# RTI-Dome-eth-RP2040.net
KiCad netlist of a schematic drawn in EAGLE
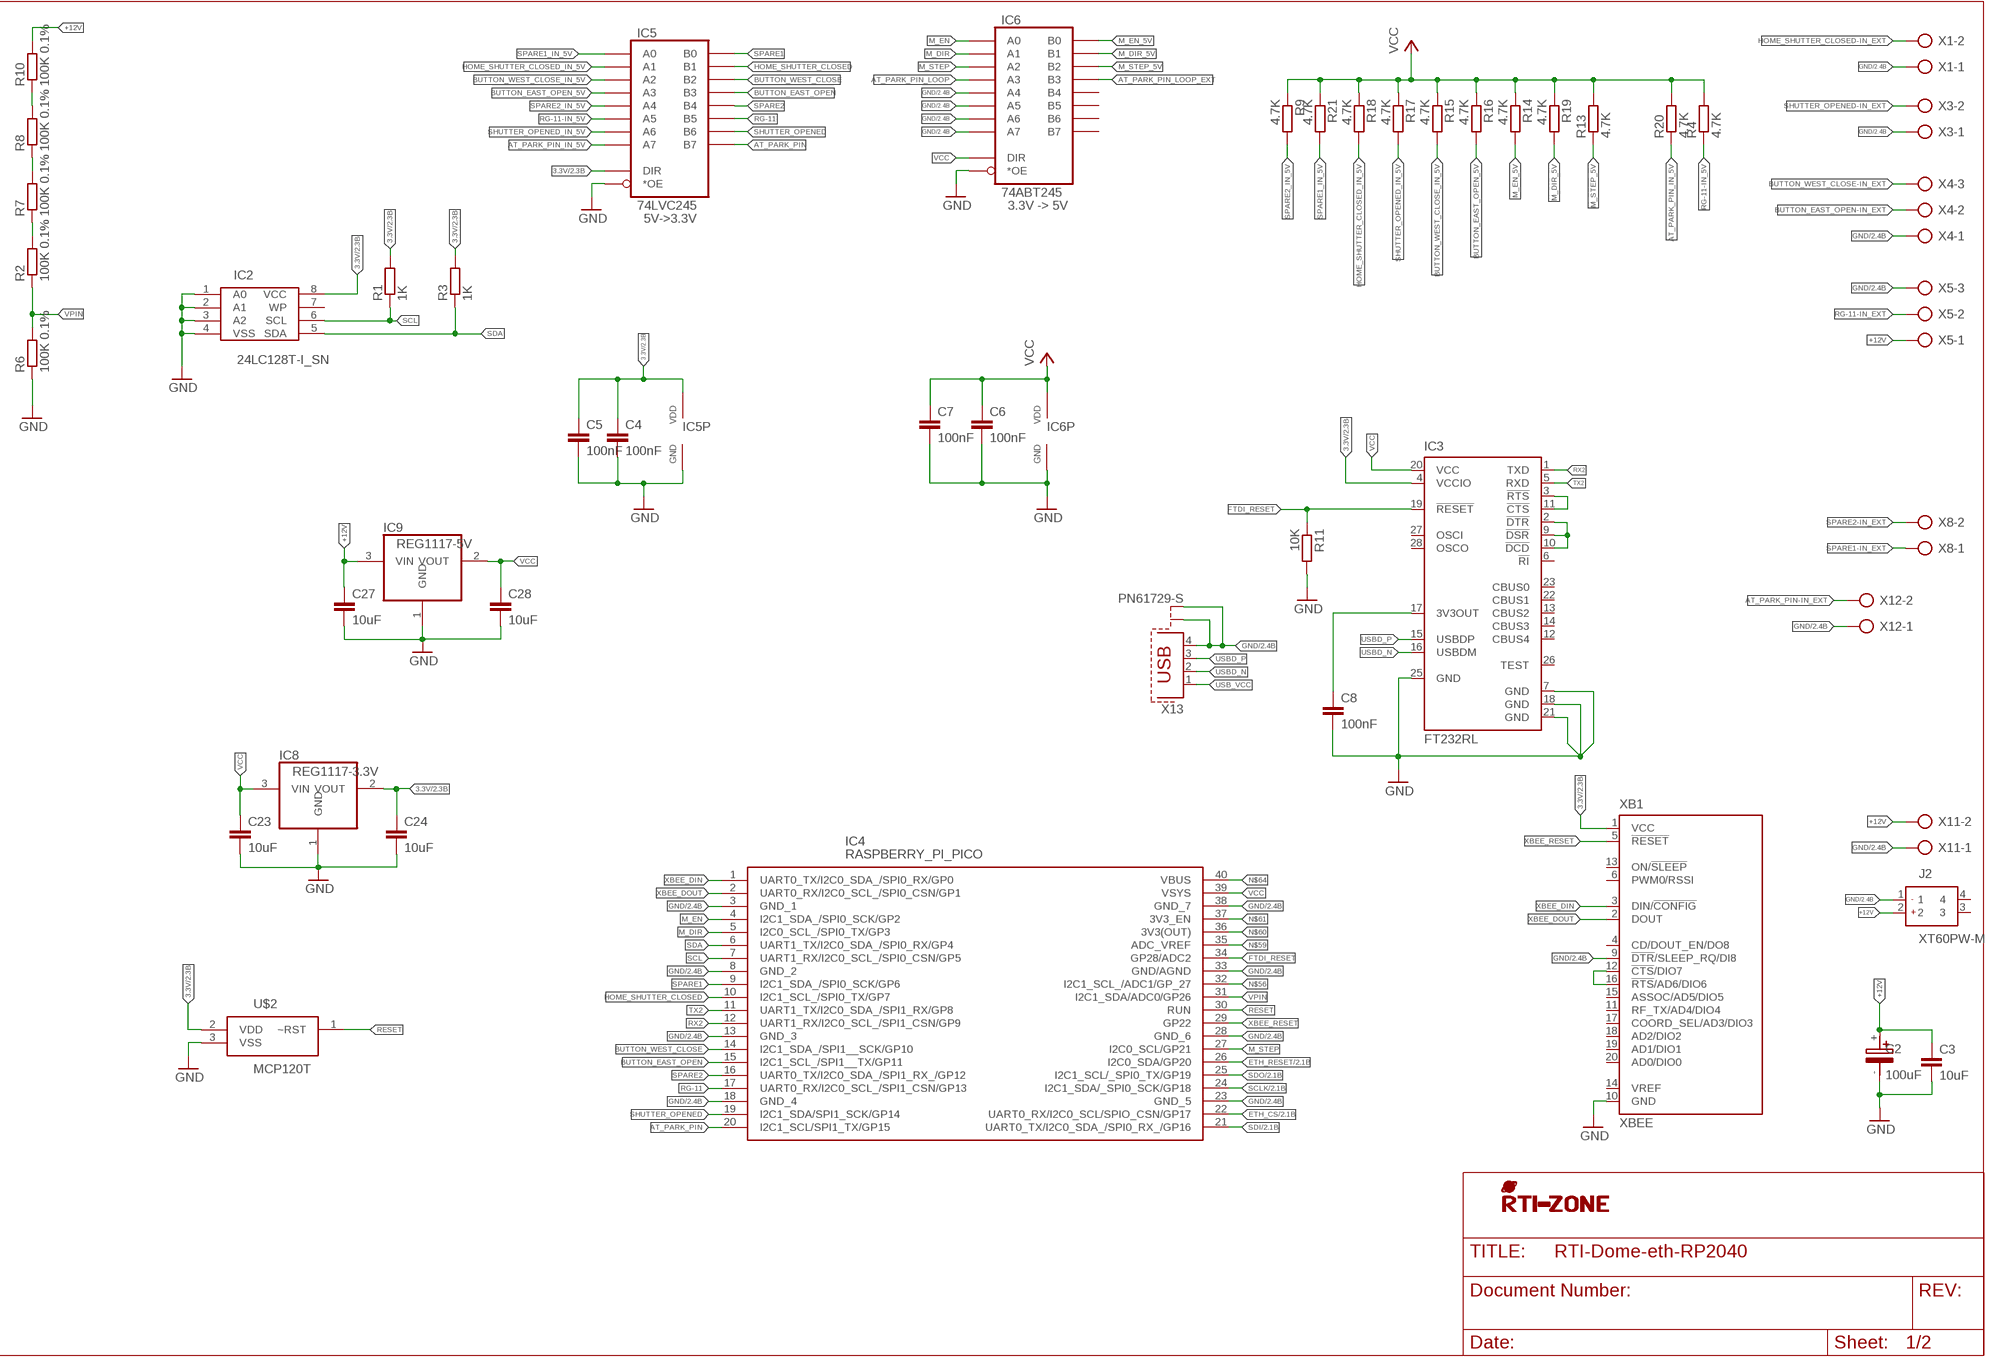
[diagram p0: schematic, sheet 1, part 1 of 2]
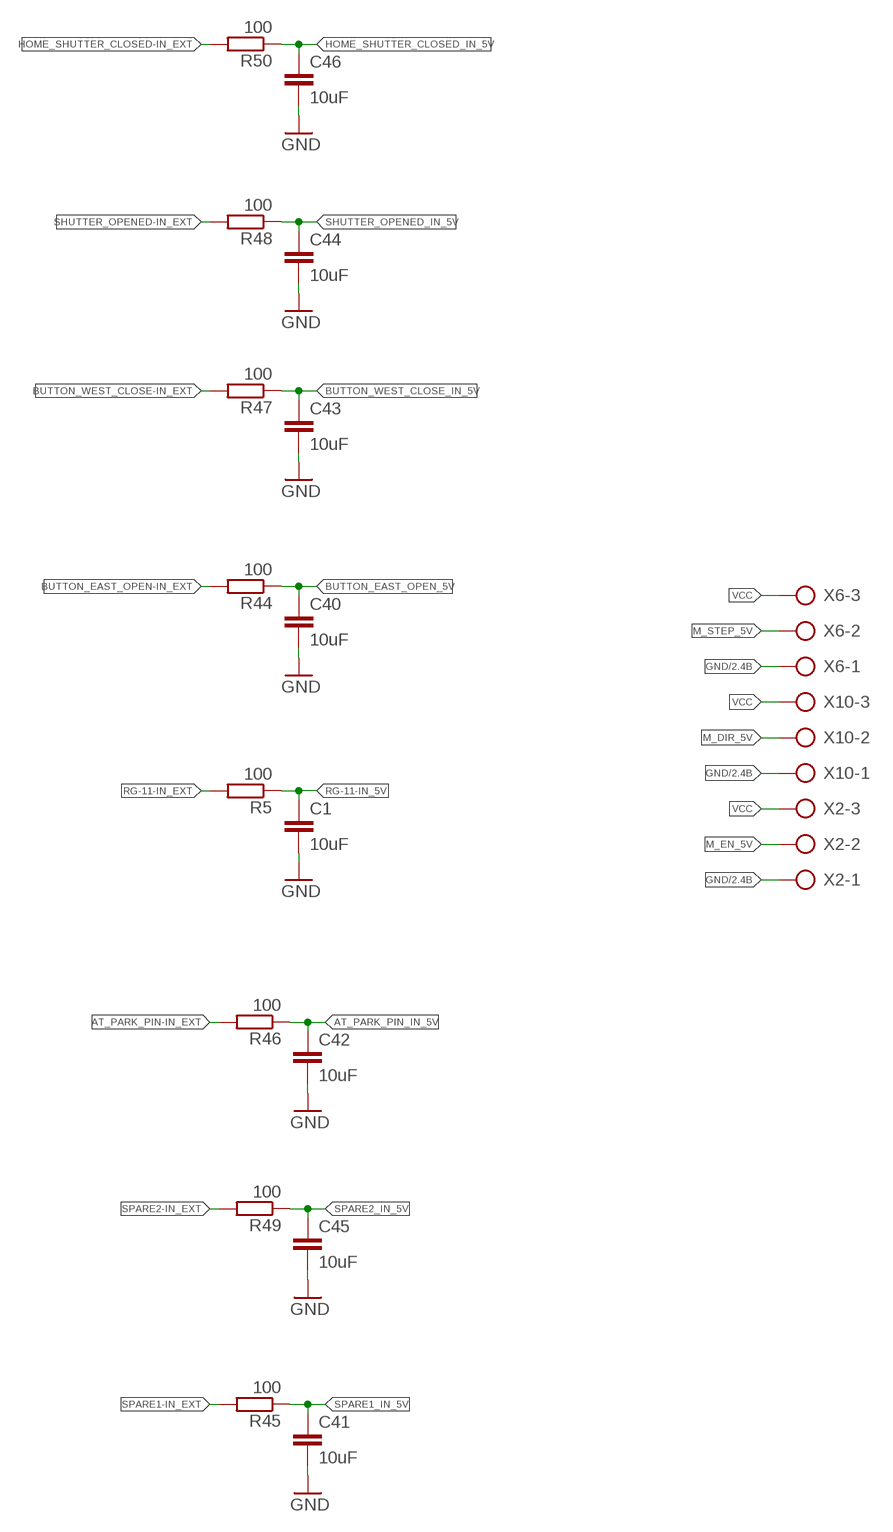
[diagram p1: schematic, sheet 1, part 2 of 2]
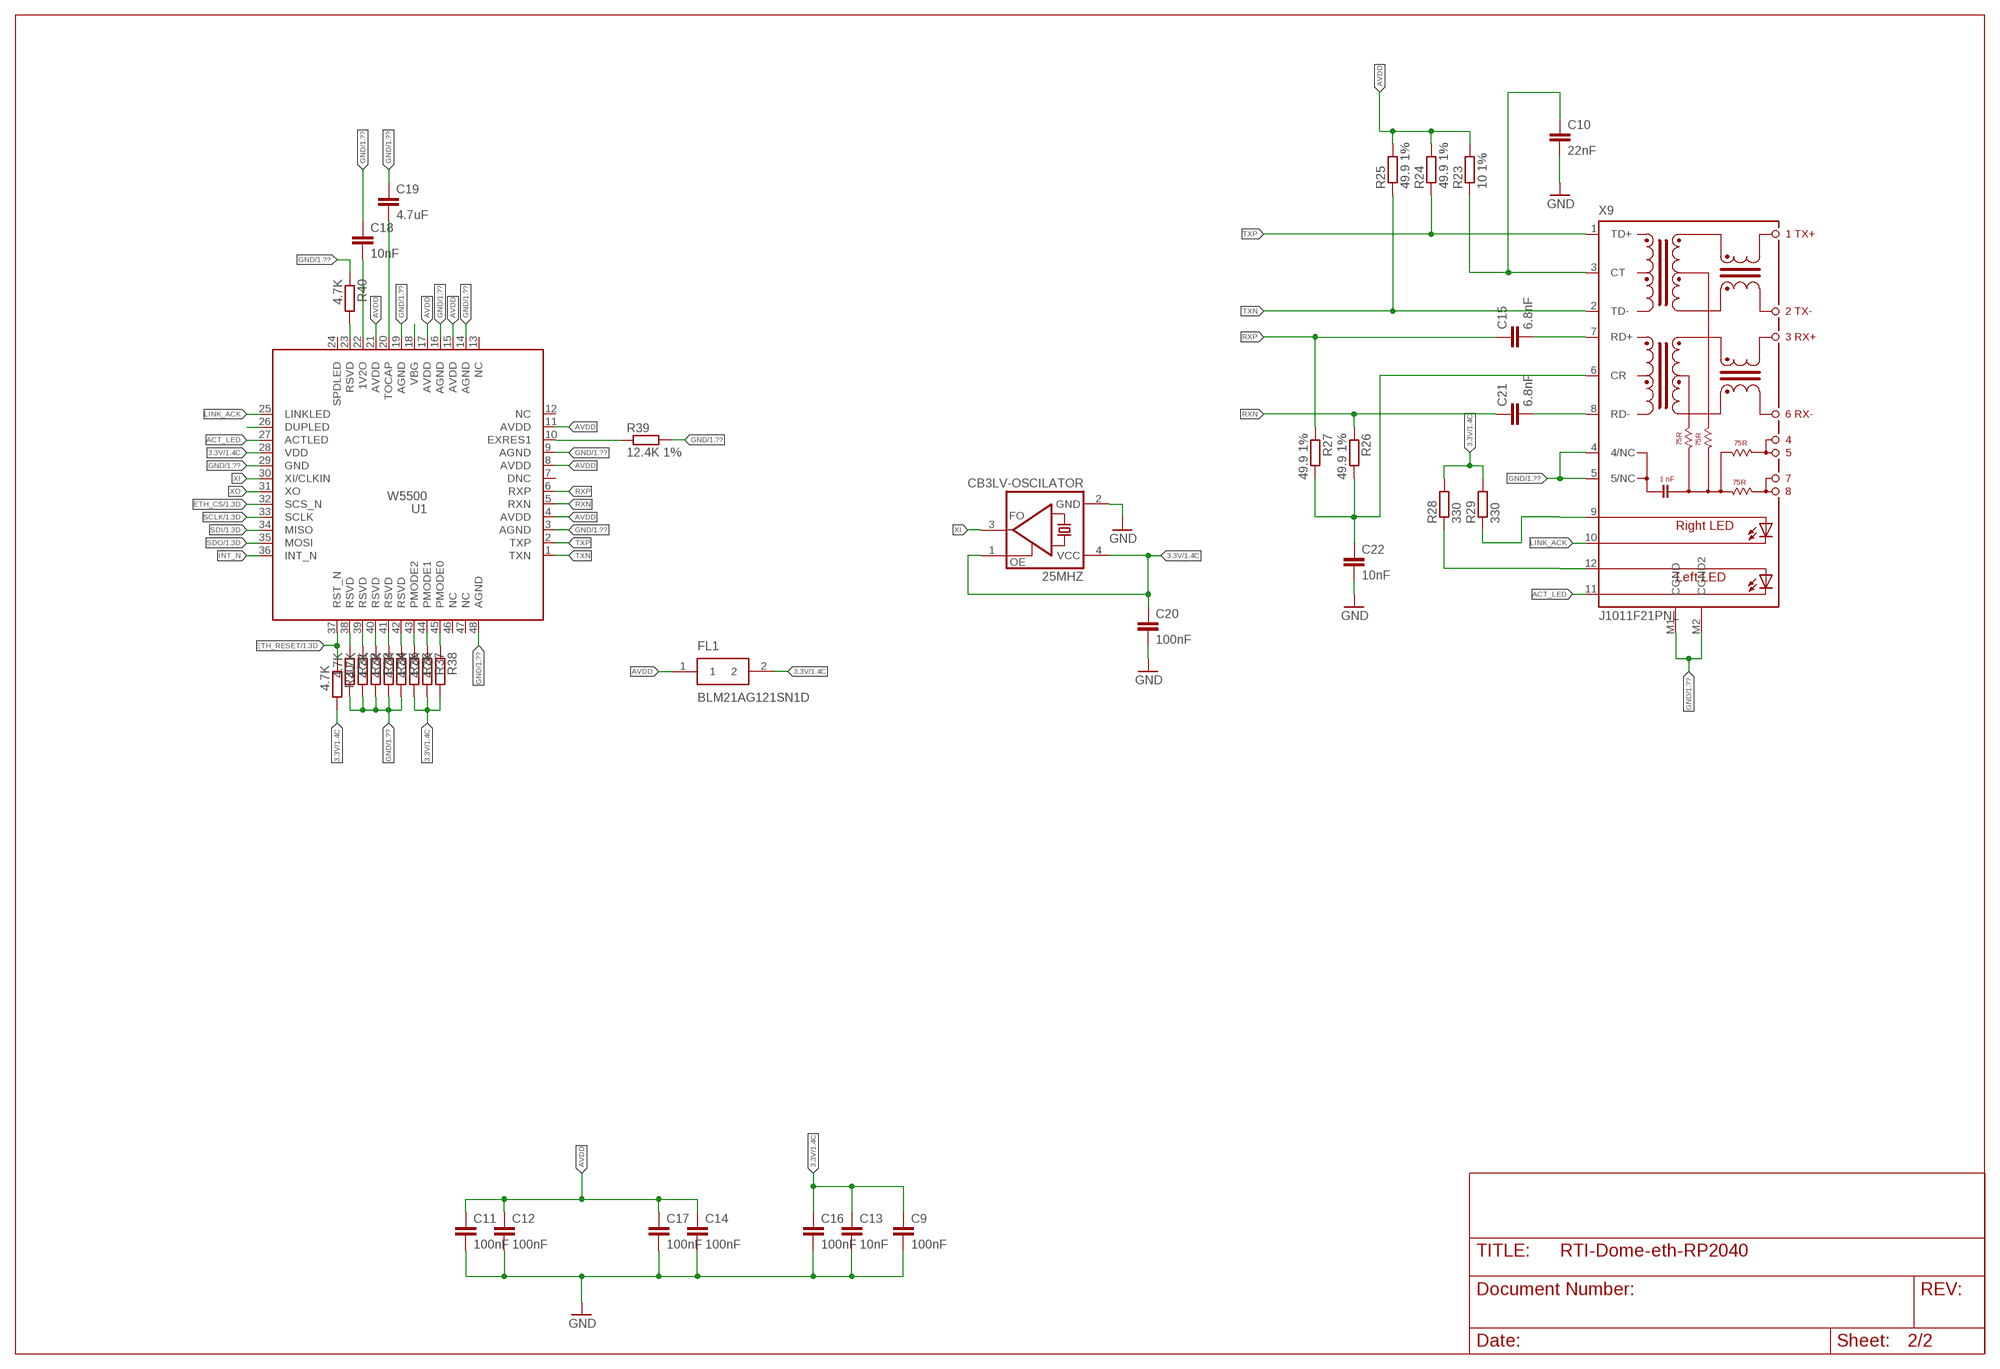
[diagram p2: schematic, sheet 2]

(export (version "E")
  (design (tool "Eeschema 10.0.6"))
  (components
    (comp (ref "C1")
      (value "10uF")
      (footprint "eagle-import:C0805")
      (fields (field (name "MPN") "CC0805KKX5R8BB106"))
      (libsource (lib "eagle-import") (part "C-EUC0805"))
    )
    (comp (ref "C2")
      (value "100uF")
      (footprint "eagle-import:UD-10X10_NICHICON")
      (fields (field (name "MPN") "MAL215099804E3"))
      (libsource (lib "eagle-import") (part "MAL215099804E3{dblquote}{dblquote}"))
    )
    (comp (ref "C3")
      (value "10uF")
      (footprint "eagle-import:C0805")
      (fields (field (name "MPN") "CC0805KKX5R8BB106"))
      (libsource (lib "eagle-import") (part "C-EUC0805"))
    )
    (comp (ref "C4")
      (value "100nF")
      (footprint "eagle-import:C0805")
      (fields (field (name "MPN") "0805YD104KAT2A"))
      (libsource (lib "eagle-import") (part "C-EUC0805"))
    )
    (comp (ref "C5")
      (value "100nF")
      (footprint "eagle-import:C0805")
      (fields (field (name "MPN") "0805YD104KAT2A"))
      (libsource (lib "eagle-import") (part "C-EUC0805"))
    )
    (comp (ref "C6")
      (value "100nF")
      (footprint "eagle-import:C0805")
      (fields (field (name "MPN") "0805YD104KAT2A"))
      (libsource (lib "eagle-import") (part "C-EUC0805"))
    )
    (comp (ref "C7")
      (value "100nF")
      (footprint "eagle-import:C0805")
      (fields (field (name "MPN") "0805YD104KAT2A"))
      (libsource (lib "eagle-import") (part "C-EUC0805"))
    )
    (comp (ref "C8")
      (value "100nF")
      (footprint "eagle-import:C0805")
      (fields (field (name "MPN") "0805YD104KAT2A"))
      (libsource (lib "eagle-import") (part "C-EUC0805"))
    )
    (comp (ref "C23")
      (value "10uF")
      (footprint "eagle-import:C0805")
      (fields (field (name "MPN") "CC0805KKX5R8BB106"))
      (libsource (lib "eagle-import") (part "C-EUC0805"))
    )
    (comp (ref "C24")
      (value "10uF")
      (footprint "eagle-import:C0805")
      (fields (field (name "MPN") "CC0805KKX5R8BB106"))
      (libsource (lib "eagle-import") (part "C-EUC0805"))
    )
    (comp (ref "C27")
      (value "10uF")
      (footprint "eagle-import:C0805")
      (fields (field (name "MPN") "CC0805KKX5R8BB106"))
      (libsource (lib "eagle-import") (part "C-EUC0805"))
    )
    (comp (ref "C28")
      (value "10uF")
      (footprint "eagle-import:C0805")
      (fields (field (name "MPN") "CC0805KKX5R8BB106"))
      (libsource (lib "eagle-import") (part "C-EUC0805"))
    )
    (comp (ref "C40")
      (value "10uF")
      (footprint "eagle-import:C0805")
      (fields (field (name "MPN") "CC0805KKX5R8BB106"))
      (libsource (lib "eagle-import") (part "C-EUC0805"))
    )
    (comp (ref "C41")
      (value "10uF")
      (footprint "eagle-import:C0805")
      (fields (field (name "MPN") "CC0805KKX5R8BB106"))
      (libsource (lib "eagle-import") (part "C-EUC0805"))
    )
    (comp (ref "C42")
      (value "10uF")
      (footprint "eagle-import:C0805")
      (fields (field (name "MPN") "CC0805KKX5R8BB106"))
      (libsource (lib "eagle-import") (part "C-EUC0805"))
    )
    (comp (ref "C43")
      (value "10uF")
      (footprint "eagle-import:C0805")
      (fields (field (name "MPN") "CC0805KKX5R8BB106"))
      (libsource (lib "eagle-import") (part "C-EUC0805"))
    )
    (comp (ref "C44")
      (value "10uF")
      (footprint "eagle-import:C0805")
      (fields (field (name "MPN") "CC0805KKX5R8BB106"))
      (libsource (lib "eagle-import") (part "C-EUC0805"))
    )
    (comp (ref "C45")
      (value "10uF")
      (footprint "eagle-import:C0805")
      (fields (field (name "MPN") "CC0805KKX5R8BB106"))
      (libsource (lib "eagle-import") (part "C-EUC0805"))
    )
    (comp (ref "C46")
      (value "10uF")
      (footprint "eagle-import:C0805")
      (fields (field (name "MPN") "CC0805KKX5R8BB106"))
      (libsource (lib "eagle-import") (part "C-EUC0805"))
    )
    (comp (ref "IC2")
      (value "24LC128T-I_SN")
      (footprint "eagle-import:SOIC127P600X175-8N")
      (fields
        (field (name "ARROW_PART_NUMBER") "24LC128T-I/SN")
        (field (name "MOUSER_PART_NUMBER") "579-24LC128T-I/SN")
      )
      (libsource (lib "eagle-import") (part "24LC128T-I_SN"))
    )
    (comp (ref "IC3")
      (value "FT232RL")
      (footprint "eagle-import:SSOP28")
      (fields (field (name "MPN") "FT232RL-REEL"))
      (libsource (lib "eagle-import") (part "FT232RL"))
    )
    (comp (ref "IC4")
      (value "RASPBERRY_PI_PICO")
      (footprint "eagle-import:RASPBERRYPIPICO")
      (description "RASPBERRY-PI - RASPBERRY PI PICO - Raspberry Pi Board, Raspberry Pi Pic, RP2040, 32bit, ARM Cortex-M0+")
      (fields
        (field (name "MANUFACTURER_PART_NUMBER") "RASPBERRY PI PICO W")
        (field (name "MANUFACTURER_NAME") "RASPBERRY-PI PICO")
        (field (name "MANUFACTURER_PART_NUMBER_1") "SC0916")
        (field (name "MOUSER_PART_NUMBER") "SC0915")
        (field (name "MPN") "SC0916")
      )
      (libsource (lib "eagle-import") (part "RASPBERRY_PI_PICO"))
    )
    (comp (ref "IC5")
      (value "74LVC245")
      (footprint "eagle-import:TSSOP20")
      (fields (field (name "MPN") "SN74LVC245APWR"))
      (libsource (lib "eagle-import") (part "74245LVC"))
    )
    (comp (ref "IC6")
      (value "74ABT245")
      (footprint "eagle-import:TSSOP20")
      (fields (field (name "MPN") "74ABT245PW,118"))
      (libsource (lib "eagle-import") (part "74245ABT"))
    )
    (comp (ref "IC8")
      (value "REG1117-3.3V")
      (footprint "eagle-import:SOT223")
      (fields (field (name "MPN") "REG1117") (field (name "MPN_1") "REG1117-3.3/2K5"))
      (libsource (lib "eagle-import") (part "REG1117"))
    )
    (comp (ref "IC9")
      (value "REG1117-5V")
      (footprint "eagle-import:SOT223")
      (fields (field (name "MPN") "REG1117") (field (name "MPN_1") "REG1117-3.3/2K5"))
      (libsource (lib "eagle-import") (part "REG1117"))
    )
    (comp (ref "J2")
      (value "XT60PW-M")
      (footprint "eagle-import:XT60PWM")
      (libsource (lib "eagle-import") (part "XT60PW-M"))
    )
    (comp (ref "R1")
      (value "1K")
      (footprint "eagle-import:R0805")
      (fields (field (name "MPN") "RT0805FRE071KL"))
      (libsource (lib "eagle-import") (part "R-EU_R0805"))
    )
    (comp (ref "R2")
      (value "100K 0.1%")
      (footprint "eagle-import:R0805")
      (fields (field (name "MPN") "AT0805BRD07100KL"))
      (libsource (lib "eagle-import") (part "R-EU_R0805"))
    )
    (comp (ref "R3")
      (value "1K")
      (footprint "eagle-import:R0805")
      (fields (field (name "MPN") "RT0805FRE071KL"))
      (libsource (lib "eagle-import") (part "R-EU_R0805"))
    )
    (comp (ref "R4")
      (value "4.7K")
      (footprint "eagle-import:R0805")
      (fields (field (name "MPN") "RT0805FRE074K7L"))
      (libsource (lib "eagle-import") (part "R-EU_R0805"))
    )
    (comp (ref "R5")
      (value "100")
      (footprint "eagle-import:R0805")
      (fields (field (name "MPN") "RT0805FRD07100RL"))
      (libsource (lib "eagle-import") (part "R-EU_R0805"))
    )
    (comp (ref "R6")
      (value "100K 0.1%")
      (footprint "eagle-import:R0805")
      (fields (field (name "MPN") "AT0805BRD07100KL"))
      (libsource (lib "eagle-import") (part "R-EU_R0805"))
    )
    (comp (ref "R7")
      (value "100K 0.1%")
      (footprint "eagle-import:R0805")
      (fields (field (name "MPN") "AT0805BRD07100KL"))
      (libsource (lib "eagle-import") (part "R-EU_R0805"))
    )
    (comp (ref "R8")
      (value "100K 0.1%")
      (footprint "eagle-import:R0805")
      (fields (field (name "MPN") "AT0805BRD07100KL"))
      (libsource (lib "eagle-import") (part "R-EU_R0805"))
    )
    (comp (ref "R9")
      (value "4.7K")
      (footprint "eagle-import:R0805")
      (fields (field (name "MPN") "RT0805FRE074K7L"))
      (libsource (lib "eagle-import") (part "R-EU_R0805"))
    )
    (comp (ref "R10")
      (value "100K 0.1%")
      (footprint "eagle-import:R0805")
      (fields (field (name "MPN") "AT0805BRD07100KL"))
      (libsource (lib "eagle-import") (part "R-EU_R0805"))
    )
    (comp (ref "R11")
      (value "10K")
      (footprint "eagle-import:R0805")
      (fields (field (name "MPN") "RT0805FRE0710KL"))
      (libsource (lib "eagle-import") (part "R-EU_R0805"))
    )
    (comp (ref "R13")
      (value "4.7K")
      (footprint "eagle-import:R0805")
      (fields (field (name "MPN") "RT0805FRE074K7L"))
      (libsource (lib "eagle-import") (part "R-EU_R0805"))
    )
    (comp (ref "R14")
      (value "4.7K")
      (footprint "eagle-import:R0805")
      (fields (field (name "MPN") "RT0805FRE074K7L"))
      (libsource (lib "eagle-import") (part "R-EU_R0805"))
    )
    (comp (ref "R15")
      (value "4.7K")
      (footprint "eagle-import:R0805")
      (fields (field (name "MPN") "RT0805FRE074K7L"))
      (libsource (lib "eagle-import") (part "R-EU_R0805"))
    )
    (comp (ref "R16")
      (value "4.7K")
      (footprint "eagle-import:R0805")
      (fields (field (name "MPN") "RT0805FRE074K7L"))
      (libsource (lib "eagle-import") (part "R-EU_R0805"))
    )
    (comp (ref "R17")
      (value "4.7K")
      (footprint "eagle-import:R0805")
      (fields (field (name "MPN") "RT0805FRE074K7L"))
      (libsource (lib "eagle-import") (part "R-EU_R0805"))
    )
    (comp (ref "R18")
      (value "4.7K")
      (footprint "eagle-import:R0805")
      (fields (field (name "MPN") "RT0805FRE074K7L"))
      (libsource (lib "eagle-import") (part "R-EU_R0805"))
    )
    (comp (ref "R19")
      (value "4.7K")
      (footprint "eagle-import:R0805")
      (fields (field (name "MPN") "RT0805FRE074K7L"))
      (libsource (lib "eagle-import") (part "R-EU_R0805"))
    )
    (comp (ref "R20")
      (value "4.7K")
      (footprint "eagle-import:R0805")
      (fields (field (name "MPN") "RT0805FRE074K7L"))
      (libsource (lib "eagle-import") (part "R-EU_R0805"))
    )
    (comp (ref "R21")
      (value "4.7K")
      (footprint "eagle-import:R0805")
      (fields (field (name "MPN") "RT0805FRE074K7L"))
      (libsource (lib "eagle-import") (part "R-EU_R0805"))
    )
    (comp (ref "R44")
      (value "100")
      (footprint "eagle-import:R0805")
      (fields (field (name "MPN") "RT0805FRD07100RL"))
      (libsource (lib "eagle-import") (part "R-EU_R0805"))
    )
    (comp (ref "R45")
      (value "100")
      (footprint "eagle-import:R0805")
      (fields (field (name "MPN") "RT0805FRD07100RL"))
      (libsource (lib "eagle-import") (part "R-EU_R0805"))
    )
    (comp (ref "R46")
      (value "100")
      (footprint "eagle-import:R0805")
      (fields (field (name "MPN") "RT0805FRD07100RL"))
      (libsource (lib "eagle-import") (part "R-EU_R0805"))
    )
    (comp (ref "R47")
      (value "100")
      (footprint "eagle-import:R0805")
      (fields (field (name "MPN") "RT0805FRD07100RL"))
      (libsource (lib "eagle-import") (part "R-EU_R0805"))
    )
    (comp (ref "R48")
      (value "100")
      (footprint "eagle-import:R0805")
      (fields (field (name "MPN") "RT0805FRD07100RL"))
      (libsource (lib "eagle-import") (part "R-EU_R0805"))
    )
    (comp (ref "R49")
      (value "100")
      (footprint "eagle-import:R0805")
      (fields (field (name "MPN") "RT0805FRD07100RL"))
      (libsource (lib "eagle-import") (part "R-EU_R0805"))
    )
    (comp (ref "R50")
      (value "100")
      (footprint "eagle-import:R0805")
      (fields (field (name "MPN") "RT0805FRD07100RL"))
      (libsource (lib "eagle-import") (part "R-EU_R0805"))
    )
    (comp (ref "U$2")
      (value "MCP120T")
      (footprint "eagle-import:SOT95P237X112-3N")
      (fields
        (field (name "MANUFACTURER_PART_NUMBER") "MCP120T-315I/TT")
        (field (name "MOUSER_PART_NUMBER") "579-MCP120T-315I/TT")
        (field (name "MPN") "MCP120T-270I/TT")
      )
      (libsource (lib "eagle-import") (part "MCP120T"))
    )
    (comp (ref "U$4")
      (value "RTI-LOGO_BIG")
      (footprint "eagle-import:LOGO_BIG")
      (libsource (lib "eagle-import") (part "RTI-LOGO_BIG"))
    )
    (comp (ref "X1")
      (value "AK500/2")
      (footprint "eagle-import:AK500_2")
      (fields (field (name "MPN") "691101710002"))
      (libsource (lib "eagle-import") (part "AK500/2"))
    )
    (comp (ref "X2")
      (value "AK500/3")
      (footprint "eagle-import:AK500_3")
      (libsource (lib "eagle-import") (part "AK500/3"))
    )
    (comp (ref "X3")
      (value "AK500/2")
      (footprint "eagle-import:AK500_2")
      (fields (field (name "MPN") "691101710002"))
      (libsource (lib "eagle-import") (part "AK500/2"))
    )
    (comp (ref "X4")
      (value "AK500/3")
      (footprint "eagle-import:AK500_3")
      (fields (field (name "MPN") "691101710003"))
      (libsource (lib "eagle-import") (part "AK500/3"))
    )
    (comp (ref "X5")
      (value "AK500/3")
      (footprint "eagle-import:AK500_3")
      (fields (field (name "MPN") "691101710003"))
      (libsource (lib "eagle-import") (part "AK500/3"))
    )
    (comp (ref "X6")
      (value "AK500/3")
      (footprint "eagle-import:AK500_3")
      (libsource (lib "eagle-import") (part "AK500/3"))
    )
    (comp (ref "X8")
      (value "AK500/2")
      (footprint "eagle-import:AK500_2")
      (fields (field (name "MPN") "691101710002"))
      (libsource (lib "eagle-import") (part "AK500/2"))
    )
    (comp (ref "X10")
      (value "AK500/3")
      (footprint "eagle-import:AK500_3")
      (libsource (lib "eagle-import") (part "AK500/3"))
    )
    (comp (ref "X11")
      (value "AK500/2")
      (footprint "eagle-import:AK500_2")
      (fields (field (name "MPN") "691101710002"))
      (libsource (lib "eagle-import") (part "AK500/2"))
    )
    (comp (ref "X12")
      (value "AK500/2")
      (footprint "eagle-import:AK500_2")
      (fields (field (name "MPN") "691101710002"))
      (libsource (lib "eagle-import") (part "AK500/2"))
    )
    (comp (ref "X13")
      (value "PN61729-S")
      (footprint "eagle-import:PN61729-S")
      (fields (field (name "MPN") "SS-52300-001"))
      (libsource (lib "eagle-import") (part "PN61729-S"))
    )
    (comp (ref "XB1")
      (value "XBEE")
      (footprint "eagle-import:XBEE")
      (fields (field (name "MPN") "XBP24-Z7UIT-004"))
      (libsource (lib "eagle-import") (part "XBEE"))
    )
    (comp (ref "25MHZ")
      (value "CB3LV-OSCILATOR")
      (footprint "eagle-import:SMD-7050_4P")
      (fields (field (name "MPN") "CB3LV-3I-25M0000"))
      (libsource (lib "eagle-import") (part "CB3LV-OSCILATOR"))
    )
    (comp (ref "C9")
      (value "100nF")
      (footprint "eagle-import:C0805")
      (fields (field (name "MPN") "0805YD104KAT2A"))
      (libsource (lib "eagle-import") (part "C-EUC0805"))
    )
    (comp (ref "C10")
      (value "22nF")
      (footprint "eagle-import:C0805")
      (fields (field (name "MPN") "CC0805JRX7R8BB223"))
      (libsource (lib "eagle-import") (part "C-EUC0805"))
    )
    (comp (ref "C11")
      (value "100nF")
      (footprint "eagle-import:C0805")
      (fields (field (name "MPN") "0805YD104KAT2A"))
      (libsource (lib "eagle-import") (part "C-EUC0805"))
    )
    (comp (ref "C12")
      (value "100nF")
      (footprint "eagle-import:C0805")
      (fields (field (name "MPN") "0805YD104KAT2A"))
      (libsource (lib "eagle-import") (part "C-EUC0805"))
    )
    (comp (ref "C13")
      (value "10nF")
      (footprint "eagle-import:C0805")
      (fields (field (name "MPN") " CC0805KRX7R9BB103"))
      (libsource (lib "eagle-import") (part "C-EUC0805"))
    )
    (comp (ref "C14")
      (value "100nF")
      (footprint "eagle-import:C0805")
      (fields (field (name "MPN") "0805YD104KAT2A"))
      (libsource (lib "eagle-import") (part "C-EUC0805"))
    )
    (comp (ref "C15")
      (value "6.8nF")
      (footprint "eagle-import:C0805")
      (fields (field (name "MPN") "C0805C682F4HACTU"))
      (libsource (lib "eagle-import") (part "C-EUC0805"))
    )
    (comp (ref "C16")
      (value "100nF")
      (footprint "eagle-import:C0805")
      (fields (field (name "MPN") "0805YD104KAT2A"))
      (libsource (lib "eagle-import") (part "C-EUC0805"))
    )
    (comp (ref "C17")
      (value "100nF")
      (footprint "eagle-import:C0805")
      (fields (field (name "MPN") "0805YD104KAT2A"))
      (libsource (lib "eagle-import") (part "C-EUC0805"))
    )
    (comp (ref "C18")
      (value "10nF")
      (footprint "eagle-import:C0805")
      (fields (field (name "MPN") " CC0805KRX7R9BB103"))
      (libsource (lib "eagle-import") (part "C-EUC0805"))
    )
    (comp (ref "C19")
      (value "4.7uF")
      (footprint "eagle-import:C0805")
      (fields (field (name "MPN") "C0805C475J3RACTU"))
      (libsource (lib "eagle-import") (part "C-EUC0805"))
    )
    (comp (ref "C20")
      (value "100nF")
      (footprint "eagle-import:C0805")
      (fields (field (name "MPN") "0805YD104KAT2A"))
      (libsource (lib "eagle-import") (part "C-EUC0805"))
    )
    (comp (ref "C21")
      (value "6.8nF")
      (footprint "eagle-import:C0805")
      (fields (field (name "MPN") "C0805C682F4HACTU"))
      (libsource (lib "eagle-import") (part "C-EUC0805"))
    )
    (comp (ref "C22")
      (value "10nF")
      (footprint "eagle-import:C0805")
      (fields (field (name "MPN") " CC0805KRX7R9BB103"))
      (libsource (lib "eagle-import") (part "C-EUC0805"))
    )
    (comp (ref "FL1")
      (value "BLM21AG121SN1D")
      (footprint "eagle-import:L0805")
      (libsource (lib "eagle-import") (part "BLM21AG121SN1D"))
    )
    (comp (ref "R23")
      (value "10 1%")
      (footprint "eagle-import:R0805")
      (fields (field (name "MPN") "RT0805FRE1310RL"))
      (libsource (lib "eagle-import") (part "R-EU_R0805"))
    )
    (comp (ref "R24")
      (value "49.9 1%")
      (footprint "eagle-import:R0805")
      (fields (field (name "MPN") "RC0805FR-0749R9L"))
      (libsource (lib "eagle-import") (part "R-EU_R0805"))
    )
    (comp (ref "R25")
      (value "49.9 1%")
      (footprint "eagle-import:R0805")
      (fields (field (name "MPN") "RC0805FR-0749R9L"))
      (libsource (lib "eagle-import") (part "R-EU_R0805"))
    )
    (comp (ref "R26")
      (value "49.9 1%")
      (footprint "eagle-import:R0805")
      (fields (field (name "MPN") "RC0805FR-0749R9L"))
      (libsource (lib "eagle-import") (part "R-EU_R0805"))
    )
    (comp (ref "R27")
      (value "49.9 1%")
      (footprint "eagle-import:R0805")
      (fields (field (name "MPN") "RC0805FR-0749R9L"))
      (libsource (lib "eagle-import") (part "R-EU_R0805"))
    )
    (comp (ref "R28")
      (value "330")
      (footprint "eagle-import:R0805")
      (fields (field (name "MPN") " RC0805JR-07330RL"))
      (libsource (lib "eagle-import") (part "R-EU_R0805"))
    )
    (comp (ref "R29")
      (value "330")
      (footprint "eagle-import:R0805")
      (fields (field (name "MPN") " RC0805JR-07330RL"))
      (libsource (lib "eagle-import") (part "R-EU_R0805"))
    )
    (comp (ref "R30")
      (value "4.7K")
      (footprint "eagle-import:R0805")
      (fields (field (name "MPN") "RT0805FRE074K7L"))
      (libsource (lib "eagle-import") (part "R-EU_R0805"))
    )
    (comp (ref "R31")
      (value "4.7K")
      (footprint "eagle-import:R0805")
      (fields (field (name "MPN") "RT0805FRE074K7L"))
      (libsource (lib "eagle-import") (part "R-EU_R0805"))
    )
    (comp (ref "R32")
      (value "4.7K")
      (footprint "eagle-import:R0805")
      (fields (field (name "MPN") "RT0805FRE074K7L"))
      (libsource (lib "eagle-import") (part "R-EU_R0805"))
    )
    (comp (ref "R33")
      (value "4.7K")
      (footprint "eagle-import:R0805")
      (fields (field (name "MPN") "RT0805FRE074K7L"))
      (libsource (lib "eagle-import") (part "R-EU_R0805"))
    )
    (comp (ref "R34")
      (value "4.7K")
      (footprint "eagle-import:R0805")
      (fields (field (name "MPN") "RT0805FRE074K7L"))
      (libsource (lib "eagle-import") (part "R-EU_R0805"))
    )
    (comp (ref "R35")
      (value "4.7K")
      (footprint "eagle-import:R0805")
      (fields (field (name "MPN") "RT0805FRE074K7L"))
      (libsource (lib "eagle-import") (part "R-EU_R0805"))
    )
    (comp (ref "R36")
      (value "4.7K")
      (footprint "eagle-import:R0805")
      (fields (field (name "MPN") "RT0805FRE074K7L"))
      (libsource (lib "eagle-import") (part "R-EU_R0805"))
    )
    (comp (ref "R37")
      (value "4.7K")
      (footprint "eagle-import:R0805")
      (fields (field (name "MPN") "RT0805FRE074K7L"))
      (libsource (lib "eagle-import") (part "R-EU_R0805"))
    )
    (comp (ref "R38")
      (value "4.7K")
      (footprint "eagle-import:R0805")
      (fields (field (name "MPN") "RT0805FRE074K7L"))
      (libsource (lib "eagle-import") (part "R-EU_R0805"))
    )
    (comp (ref "R39")
      (value "12.4K 1%")
      (footprint "eagle-import:R0805")
      (fields (field (name "MPN") "RC0805FR-0712K4L"))
      (libsource (lib "eagle-import") (part "R-EU_R0805"))
    )
    (comp (ref "R40")
      (value "4.7K")
      (footprint "eagle-import:R0805")
      (fields (field (name "MPN") "RT0805FRE074K7L"))
      (libsource (lib "eagle-import") (part "R-EU_R0805"))
    )
    (comp (ref "U1")
      (value "W5500")
      (footprint "eagle-import:LQFP48")
      (libsource (lib "eagle-import") (part "W5500"))
    )
    (comp (ref "X9")
      (value "J1011F21PNL")
      (footprint "eagle-import:J1011F21PNL")
      (fields (field (name "MPN") "J1011F21PNL"))
      (libsource (lib "eagle-import") (part "J1011F21PNL"))
    )
  )
  (nets
    (net (code "1") (name "+12V") (class "Default")
      (node (ref "C2") (pin "+") (pinfunction "+_+") (pintype "bidirectional"))
      (node (ref "C27") (pin "1") (pinfunction "1_1") (pintype "passive"))
      (node (ref "C3") (pin "1") (pinfunction "1_1") (pintype "passive"))
      (node (ref "IC9") (pin "3") (pinfunction "VIN_3") (pintype "input"))
      (node (ref "J2") (pin "2") (pinfunction "2_2") (pintype "bidirectional"))
      (node (ref "R10") (pin "2") (pinfunction "2_2") (pintype "passive"))
      (node (ref "X11") (pin "2") (pinfunction "KL_2") (pintype "passive"))
      (node (ref "X5") (pin "1") (pinfunction "KL_1") (pintype "passive"))
    )
    (net (code "2") (name "3.3V") (class "Default")
      (node (ref "25MHZ") (pin "1") (pinfunction "OE_1") (pintype "input"))
      (node (ref "25MHZ") (pin "4") (pinfunction "VDD_4") (pintype "power_in"))
      (node (ref "C13") (pin "1") (pinfunction "1_1") (pintype "passive"))
      (node (ref "C16") (pin "1") (pinfunction "1_1") (pintype "passive"))
      (node (ref "C20") (pin "1") (pinfunction "1_1") (pintype "passive"))
      (node (ref "C24") (pin "1") (pinfunction "1_1") (pintype "passive"))
      (node (ref "C4") (pin "1") (pinfunction "1_1") (pintype "passive"))
      (node (ref "C5") (pin "1") (pinfunction "1_1") (pintype "passive"))
      (node (ref "C9") (pin "1") (pinfunction "1_1") (pintype "passive"))
      (node (ref "FL1") (pin "2") (pinfunction "2_2") (pintype "bidirectional"))
      (node (ref "IC2") (pin "8") (pinfunction "VCC_8") (pintype "bidirectional"))
      (node (ref "IC3") (pin "4") (pinfunction "VCCIO_4") (pintype "power_in"))
      (node (ref "IC5") (pin "P$1") (pinfunction "DIR_P$1") (pintype "input"))
      (node (ref "IC5") (pin "P$20") (pinfunction "VDD_P$20") (pintype "power_in"))
      (node (ref "IC8") (pin "2") (pinfunction "VOUT_2") (pintype "output"))
      (node (ref "R1") (pin "2") (pinfunction "2_2") (pintype "passive"))
      (node (ref "R28") (pin "2") (pinfunction "2_2") (pintype "passive"))
      (node (ref "R29") (pin "2") (pinfunction "2_2") (pintype "passive"))
      (node (ref "R3") (pin "2") (pinfunction "2_2") (pintype "passive"))
      (node (ref "R30") (pin "2") (pinfunction "2_2") (pintype "passive"))
      (node (ref "R36") (pin "2") (pinfunction "2_2") (pintype "passive"))
      (node (ref "R37") (pin "2") (pinfunction "2_2") (pintype "passive"))
      (node (ref "R38") (pin "2") (pinfunction "2_2") (pintype "passive"))
      (node (ref "U$2") (pin "2") (pinfunction "VDD_2") (pintype "bidirectional"))
      (node (ref "U1") (pin "28") (pinfunction "VDD_28") (pintype "passive"))
      (node (ref "XB1") (pin "1") (pinfunction "VCC_1") (pintype "power_in"))
    )
    (net (code "3") (name "ACT_LED") (class "Default")
      (node (ref "U1") (pin "27") (pinfunction "ACTLED_27") (pintype "passive"))
      (node (ref "X9") (pin "11") (pinfunction "C-L_11") (pintype "passive"))
    )
    (net (code "4") (name "AT_PARK_PIN") (class "Default")
      (node (ref "IC4") (pin "20") (pinfunction "I2C1_SCL/SPI1_TX/GP15_20") (pintype "bidirectional"))
      (node (ref "IC5") (pin "P$11") (pinfunction "B7_P$11") (pintype "bidirectional"))
    )
    (net (code "5") (name "AT_PARK_PIN-IN_EXT") (class "Default")
      (node (ref "R46") (pin "2") (pinfunction "2_2") (pintype "passive"))
      (node (ref "X12") (pin "2") (pinfunction "KL_2") (pintype "passive"))
    )
    (net (code "6") (name "AT_PARK_PIN_IN_5V") (class "Default")
      (node (ref "C42") (pin "1") (pinfunction "1_1") (pintype "passive"))
      (node (ref "IC5") (pin "P$9") (pinfunction "A7_P$9") (pintype "bidirectional"))
      (node (ref "R20") (pin "1") (pinfunction "1_1") (pintype "passive"))
      (node (ref "R46") (pin "1") (pinfunction "1_1") (pintype "passive"))
    )
    (net (code "7") (name "AT_PARK_PIN_LOOP") (class "Default")
      (node (ref "IC6") (pin "P$5") (pinfunction "A3_P$5") (pintype "bidirectional"))
    )
    (net (code "8") (name "AT_PARK_PIN_LOOP_EXT") (class "Default")
      (node (ref "IC6") (pin "P$15") (pinfunction "B3_P$15") (pintype "bidirectional"))
    )
    (net (code "9") (name "AVDD") (class "Default")
      (node (ref "C11") (pin "1") (pinfunction "1_1") (pintype "passive"))
      (node (ref "C12") (pin "1") (pinfunction "1_1") (pintype "passive"))
      (node (ref "C14") (pin "1") (pinfunction "1_1") (pintype "passive"))
      (node (ref "C17") (pin "1") (pinfunction "1_1") (pintype "passive"))
      (node (ref "FL1") (pin "1") (pinfunction "1_1") (pintype "bidirectional"))
      (node (ref "R23") (pin "2") (pinfunction "2_2") (pintype "passive"))
      (node (ref "R24") (pin "2") (pinfunction "2_2") (pintype "passive"))
      (node (ref "R25") (pin "2") (pinfunction "2_2") (pintype "passive"))
      (node (ref "U1") (pin "11") (pinfunction "AVDD_11") (pintype "passive"))
      (node (ref "U1") (pin "15") (pinfunction "AVDD_15") (pintype "passive"))
      (node (ref "U1") (pin "17") (pinfunction "AVDD_17") (pintype "passive"))
      (node (ref "U1") (pin "21") (pinfunction "AVDD_21") (pintype "passive"))
      (node (ref "U1") (pin "4") (pinfunction "AVDD_4") (pintype "passive"))
      (node (ref "U1") (pin "8") (pinfunction "AVDD_8") (pintype "passive"))
    )
    (net (code "10") (name "BUTTON_EAST_OPEN") (class "Default")
      (node (ref "IC4") (pin "15") (pinfunction "I2C1_SCL_/SPI1__TX/GP11_15") (pintype "bidirectional"))
      (node (ref "IC5") (pin "P$15") (pinfunction "B3_P$15") (pintype "bidirectional"))
    )
    (net (code "11") (name "BUTTON_EAST_OPEN-IN_EXT") (class "Default")
      (node (ref "R44") (pin "2") (pinfunction "2_2") (pintype "passive"))
      (node (ref "X4") (pin "2") (pinfunction "KL_2") (pintype "passive"))
    )
    (net (code "12") (name "BUTTON_EAST_OPEN_5V") (class "Default")
      (node (ref "C40") (pin "1") (pinfunction "1_1") (pintype "passive"))
      (node (ref "IC5") (pin "P$5") (pinfunction "A3_P$5") (pintype "bidirectional"))
      (node (ref "R16") (pin "2") (pinfunction "2_2") (pintype "passive"))
      (node (ref "R44") (pin "1") (pinfunction "1_1") (pintype "passive"))
    )
    (net (code "13") (name "BUTTON_WEST_CLOSE") (class "Default")
      (node (ref "IC4") (pin "14") (pinfunction "I2C1_SDA_/SPI1__SCK/GP10_14") (pintype "bidirectional"))
      (node (ref "IC5") (pin "P$16") (pinfunction "B2_P$16") (pintype "bidirectional"))
    )
    (net (code "14") (name "BUTTON_WEST_CLOSE-IN_EXT") (class "Default")
      (node (ref "R47") (pin "2") (pinfunction "2_2") (pintype "passive"))
      (node (ref "X4") (pin "3") (pinfunction "KL_3") (pintype "passive"))
    )
    (net (code "15") (name "BUTTON_WEST_CLOSE_IN_5V") (class "Default")
      (node (ref "C43") (pin "1") (pinfunction "1_1") (pintype "passive"))
      (node (ref "IC5") (pin "P$4") (pinfunction "A2_P$4") (pintype "bidirectional"))
      (node (ref "R15") (pin "2") (pinfunction "2_2") (pintype "passive"))
      (node (ref "R47") (pin "1") (pinfunction "1_1") (pintype "passive"))
    )
    (net (code "16") (name "ETH_CS") (class "Default")
      (node (ref "IC4") (pin "22") (pinfunction "UART0_RX/I2C0_SCL/SPIO_CSN/GP17_22") (pintype "bidirectional"))
      (node (ref "U1") (pin "32") (pinfunction "SCS_N_32") (pintype "passive"))
    )
    (net (code "17") (name "ETH_RESET") (class "Default")
      (node (ref "IC4") (pin "26") (pinfunction "I2C0_SDA/GP20_26") (pintype "bidirectional"))
      (node (ref "R30") (pin "1") (pinfunction "1_1") (pintype "passive"))
      (node (ref "U1") (pin "37") (pinfunction "RST_N_37") (pintype "passive"))
    )
    (net (code "18") (name "FTDI_RESET") (class "Default")
      (node (ref "IC3") (pin "19") (pinfunction "~{RESET}_19") (pintype "input"))
      (node (ref "IC4") (pin "34") (pinfunction "GP28/ADC2_34") (pintype "bidirectional"))
      (node (ref "R11") (pin "1") (pinfunction "1_1") (pintype "passive"))
    )
    (net (code "19") (name "GND") (class "Default")
      (node (ref "25MHZ") (pin "2") (pinfunction "GND_2") (pintype "power_in"))
      (node (ref "C1") (pin "2") (pinfunction "2_2") (pintype "passive"))
      (node (ref "C10") (pin "2") (pinfunction "2_2") (pintype "passive"))
      (node (ref "C11") (pin "2") (pinfunction "2_2") (pintype "passive"))
      (node (ref "C12") (pin "2") (pinfunction "2_2") (pintype "passive"))
      (node (ref "C13") (pin "2") (pinfunction "2_2") (pintype "passive"))
      (node (ref "C14") (pin "2") (pinfunction "2_2") (pintype "passive"))
      (node (ref "C16") (pin "2") (pinfunction "2_2") (pintype "passive"))
      (node (ref "C17") (pin "2") (pinfunction "2_2") (pintype "passive"))
      (node (ref "C18") (pin "1") (pinfunction "1_1") (pintype "passive"))
      (node (ref "C19") (pin "1") (pinfunction "1_1") (pintype "passive"))
      (node (ref "C2") (pin "-") (pinfunction "-_-") (pintype "bidirectional"))
      (node (ref "C20") (pin "2") (pinfunction "2_2") (pintype "passive"))
      (node (ref "C22") (pin "2") (pinfunction "2_2") (pintype "passive"))
      (node (ref "C23") (pin "2") (pinfunction "2_2") (pintype "passive"))
      (node (ref "C24") (pin "2") (pinfunction "2_2") (pintype "passive"))
      (node (ref "C27") (pin "2") (pinfunction "2_2") (pintype "passive"))
      (node (ref "C28") (pin "2") (pinfunction "2_2") (pintype "passive"))
      (node (ref "C3") (pin "2") (pinfunction "2_2") (pintype "passive"))
      (node (ref "C4") (pin "2") (pinfunction "2_2") (pintype "passive"))
      (node (ref "C40") (pin "2") (pinfunction "2_2") (pintype "passive"))
      (node (ref "C41") (pin "2") (pinfunction "2_2") (pintype "passive"))
      (node (ref "C42") (pin "2") (pinfunction "2_2") (pintype "passive"))
      (node (ref "C43") (pin "2") (pinfunction "2_2") (pintype "passive"))
      (node (ref "C44") (pin "2") (pinfunction "2_2") (pintype "passive"))
      (node (ref "C45") (pin "2") (pinfunction "2_2") (pintype "passive"))
      (node (ref "C46") (pin "2") (pinfunction "2_2") (pintype "passive"))
      (node (ref "C5") (pin "2") (pinfunction "2_2") (pintype "passive"))
      (node (ref "C6") (pin "2") (pinfunction "2_2") (pintype "passive"))
      (node (ref "C7") (pin "2") (pinfunction "2_2") (pintype "passive"))
      (node (ref "C8") (pin "2") (pinfunction "2_2") (pintype "passive"))
      (node (ref "C9") (pin "2") (pinfunction "2_2") (pintype "passive"))
      (node (ref "IC2") (pin "1") (pinfunction "A0_1") (pintype "bidirectional"))
      (node (ref "IC2") (pin "2") (pinfunction "A1_2") (pintype "bidirectional"))
      (node (ref "IC2") (pin "3") (pinfunction "A2_3") (pintype "bidirectional"))
      (node (ref "IC2") (pin "4") (pinfunction "VSS_4") (pintype "bidirectional"))
      (node (ref "IC3") (pin "18") (pinfunction "GND_18") (pintype "power_in"))
      (node (ref "IC3") (pin "21") (pinfunction "GND_21") (pintype "power_in"))
      (node (ref "IC3") (pin "25") (pinfunction "GND_25") (pintype "power_in"))
      (node (ref "IC3") (pin "7") (pinfunction "GND_7") (pintype "power_in"))
      (node (ref "IC4") (pin "13") (pinfunction "GND_3_13") (pintype "bidirectional"))
      (node (ref "IC4") (pin "18") (pinfunction "GND_4_18") (pintype "bidirectional"))
      (node (ref "IC4") (pin "23") (pinfunction "GND_5_23") (pintype "bidirectional"))
      (node (ref "IC4") (pin "28") (pinfunction "GND_6_28") (pintype "bidirectional"))
      (node (ref "IC4") (pin "3") (pinfunction "GND_1_3") (pintype "bidirectional"))
      (node (ref "IC4") (pin "33") (pinfunction "GND/AGND_33") (pintype "bidirectional"))
      (node (ref "IC4") (pin "38") (pinfunction "GND_7_38") (pintype "bidirectional"))
      (node (ref "IC4") (pin "8") (pinfunction "GND_2_8") (pintype "bidirectional"))
      (node (ref "IC5") (pin "P$10") (pinfunction "GND_P$10") (pintype "power_in"))
      (node (ref "IC5") (pin "P$19") (pinfunction "*OE_P$19") (pintype "input"))
      (node (ref "IC6") (pin "P$10") (pinfunction "GND_P$10") (pintype "power_in"))
      (node (ref "IC6") (pin "P$19") (pinfunction "*OE_P$19") (pintype "input"))
      (node (ref "IC6") (pin "P$6") (pinfunction "A4_P$6") (pintype "bidirectional"))
      (node (ref "IC6") (pin "P$7") (pinfunction "A5_P$7") (pintype "bidirectional"))
      (node (ref "IC6") (pin "P$8") (pinfunction "A6_P$8") (pintype "bidirectional"))
      (node (ref "IC6") (pin "P$9") (pinfunction "A7_P$9") (pintype "bidirectional"))
      (node (ref "IC8") (pin "1") (pinfunction "GND_1") (pintype "power_in"))
      (node (ref "IC9") (pin "1") (pinfunction "GND_1") (pintype "power_in"))
      (node (ref "J2") (pin "1") (pinfunction "1_1") (pintype "bidirectional"))
      (node (ref "R11") (pin "2") (pinfunction "2_2") (pintype "passive"))
      (node (ref "R31") (pin "2") (pinfunction "2_2") (pintype "passive"))
      (node (ref "R32") (pin "2") (pinfunction "2_2") (pintype "passive"))
      (node (ref "R33") (pin "2") (pinfunction "2_2") (pintype "passive"))
      (node (ref "R34") (pin "2") (pinfunction "2_2") (pintype "passive"))
      (node (ref "R35") (pin "2") (pinfunction "2_2") (pintype "passive"))
      (node (ref "R39") (pin "2") (pinfunction "2_2") (pintype "passive"))
      (node (ref "R40") (pin "1") (pinfunction "1_1") (pintype "passive"))
      (node (ref "R6") (pin "1") (pinfunction "1_1") (pintype "passive"))
      (node (ref "U$2") (pin "3") (pinfunction "VSS_3") (pintype "bidirectional"))
      (node (ref "U1") (pin "14") (pinfunction "AGND_14") (pintype "passive"))
      (node (ref "U1") (pin "16") (pinfunction "AGND_16") (pintype "passive"))
      (node (ref "U1") (pin "19") (pinfunction "AGND_19") (pintype "passive"))
      (node (ref "U1") (pin "29") (pinfunction "GND_29") (pintype "passive"))
      (node (ref "U1") (pin "3") (pinfunction "AGND_3") (pintype "passive"))
      (node (ref "U1") (pin "48") (pinfunction "AGND_48") (pintype "passive"))
      (node (ref "U1") (pin "9") (pinfunction "AGND_9") (pintype "passive"))
      (node (ref "X1") (pin "1") (pinfunction "KL_1") (pintype "passive"))
      (node (ref "X10") (pin "1") (pinfunction "KL_1") (pintype "passive"))
      (node (ref "X11") (pin "1") (pinfunction "KL_1") (pintype "passive"))
      (node (ref "X12") (pin "1") (pinfunction "KL_1") (pintype "passive"))
      (node (ref "X13") (pin "4") (pinfunction "4_4") (pintype "passive"))
      (node (ref "X13") (pin "S1") (pinfunction "S1_S1") (pintype "passive"))
      (node (ref "X13") (pin "S2") (pinfunction "S2_S2") (pintype "passive"))
      (node (ref "X2") (pin "1") (pinfunction "KL_1") (pintype "passive"))
      (node (ref "X3") (pin "1") (pinfunction "KL_1") (pintype "passive"))
      (node (ref "X4") (pin "1") (pinfunction "KL_1") (pintype "passive"))
      (node (ref "X5") (pin "3") (pinfunction "KL_3") (pintype "passive"))
      (node (ref "X6") (pin "1") (pinfunction "KL_1") (pintype "passive"))
      (node (ref "X9") (pin "4") (pinfunction "4/NC_4") (pintype "input"))
      (node (ref "X9") (pin "5") (pinfunction "5/NC_5") (pintype "input"))
      (node (ref "X9") (pin "M1") (pinfunction "CGND_M1") (pintype "bidirectional"))
      (node (ref "X9") (pin "M2") (pinfunction "CGND2_M2") (pintype "bidirectional"))
      (node (ref "XB1") (pin "10") (pinfunction "GND_10") (pintype "power_in"))
      (node (ref "XB1") (pin "9") (pinfunction "~{DTR}/SLEEP_RQ/DI8_9") (pintype "bidirectional"))
    )
    (net (code "20") (name "HOME_SHUTTER_CLOSED") (class "Default")
      (node (ref "IC4") (pin "10") (pinfunction "I2C1_SCL_/SPI0_TX/GP7_10") (pintype "bidirectional"))
      (node (ref "IC5") (pin "P$17") (pinfunction "B1_P$17") (pintype "bidirectional"))
    )
    (net (code "21") (name "HOME_SHUTTER_CLOSED-IN_EXT") (class "Default")
      (node (ref "R50") (pin "2") (pinfunction "2_2") (pintype "passive"))
      (node (ref "X1") (pin "2") (pinfunction "KL_2") (pintype "passive"))
    )
    (net (code "22") (name "HOME_SHUTTER_CLOSED_IN_5V") (class "Default")
      (node (ref "C46") (pin "1") (pinfunction "1_1") (pintype "passive"))
      (node (ref "IC5") (pin "P$3") (pinfunction "A1_P$3") (pintype "bidirectional"))
      (node (ref "R18") (pin "2") (pinfunction "2_2") (pintype "passive"))
      (node (ref "R50") (pin "1") (pinfunction "1_1") (pintype "passive"))
    )
    (net (code "23") (name "INT_N") (class "Default")
      (node (ref "U1") (pin "36") (pinfunction "INT_N_36") (pintype "passive"))
    )
    (net (code "24") (name "LINK_ACK") (class "Default")
      (node (ref "U1") (pin "25") (pinfunction "LINKLED_25") (pintype "passive"))
      (node (ref "X9") (pin "10") (pinfunction "C-R_10") (pintype "passive"))
    )
    (net (code "25") (name "M_DIR") (class "Default")
      (node (ref "IC4") (pin "5") (pinfunction "I2C0_SCL_/SPI0_TX/GP3_5") (pintype "bidirectional"))
      (node (ref "IC6") (pin "P$3") (pinfunction "A1_P$3") (pintype "bidirectional"))
    )
    (net (code "26") (name "M_DIR_5V") (class "Default")
      (node (ref "IC6") (pin "P$17") (pinfunction "B1_P$17") (pintype "bidirectional"))
      (node (ref "R19") (pin "2") (pinfunction "2_2") (pintype "passive"))
      (node (ref "X10") (pin "2") (pinfunction "KL_2") (pintype "passive"))
    )
    (net (code "27") (name "M_EN") (class "Default")
      (node (ref "IC4") (pin "4") (pinfunction "I2C1_SDA_/SPI0_SCK/GP2_4") (pintype "bidirectional"))
      (node (ref "IC6") (pin "P$2") (pinfunction "A0_P$2") (pintype "bidirectional"))
    )
    (net (code "28") (name "M_EN_5V") (class "Default")
      (node (ref "IC6") (pin "P$18") (pinfunction "B0_P$18") (pintype "bidirectional"))
      (node (ref "R14") (pin "2") (pinfunction "2_2") (pintype "passive"))
      (node (ref "X2") (pin "2") (pinfunction "KL_2") (pintype "passive"))
    )
    (net (code "29") (name "M_STEP") (class "Default")
      (node (ref "IC4") (pin "27") (pinfunction "I2C0_SCL/GP21_27") (pintype "bidirectional"))
      (node (ref "IC6") (pin "P$4") (pinfunction "A2_P$4") (pintype "bidirectional"))
    )
    (net (code "30") (name "M_STEP_5V") (class "Default")
      (node (ref "IC6") (pin "P$16") (pinfunction "B2_P$16") (pintype "bidirectional"))
      (node (ref "R13") (pin "1") (pinfunction "1_1") (pintype "passive"))
      (node (ref "X6") (pin "2") (pinfunction "KL_2") (pintype "passive"))
    )
    (net (code "31") (name "N$56") (class "Default")
      (node (ref "IC4") (pin "32") (pinfunction "I2C1_SCL_/ADC1/GP_27_32") (pintype "bidirectional"))
    )
    (net (code "32") (name "N$59") (class "Default")
      (node (ref "IC4") (pin "35") (pinfunction "ADC_VREF_35") (pintype "bidirectional"))
    )
    (net (code "33") (name "N$60") (class "Default")
      (node (ref "IC4") (pin "36") (pinfunction "3V3(OUT)_36") (pintype "bidirectional"))
    )
    (net (code "34") (name "N$61") (class "Default")
      (node (ref "IC4") (pin "37") (pinfunction "3V3_EN_37") (pintype "bidirectional"))
    )
    (net (code "35") (name "N$64") (class "Default")
      (node (ref "IC4") (pin "40") (pinfunction "VBUS_40") (pintype "bidirectional"))
    )
    (net (code "36") (name "Net-(IC3-3V3OUT)") (class "Default")
      (node (ref "C8") (pin "1") (pinfunction "1_1") (pintype "passive"))
      (node (ref "IC3") (pin "17") (pinfunction "3V3OUT_17") (pintype "output"))
    )
    (net (code "37") (name "Net-(IC3-~{CTS})") (class "Default")
      (node (ref "IC3") (pin "11") (pinfunction "~{CTS}_11") (pintype "input"))
      (node (ref "IC3") (pin "3") (pinfunction "~{RTS}_3") (pintype "output"))
    )
    (net (code "38") (name "Net-(IC3-~{DCD})") (class "Default")
      (node (ref "IC3") (pin "10") (pinfunction "~{DCD}_10") (pintype "input"))
      (node (ref "IC3") (pin "2") (pinfunction "~{DTR}_2") (pintype "output"))
      (node (ref "IC3") (pin "9") (pinfunction "~{DSR}_9") (pintype "input"))
    )
    (net (code "39") (name "Net-(R2-Pad2)") (class "Default")
      (node (ref "R2") (pin "2") (pinfunction "2_2") (pintype "passive"))
      (node (ref "R7") (pin "1") (pinfunction "1_1") (pintype "passive"))
    )
    (net (code "40") (name "Net-(R7-Pad2)") (class "Default")
      (node (ref "R7") (pin "2") (pinfunction "2_2") (pintype "passive"))
      (node (ref "R8") (pin "1") (pinfunction "1_1") (pintype "passive"))
    )
    (net (code "41") (name "Net-(R10-Pad1)") (class "Default")
      (node (ref "R10") (pin "1") (pinfunction "1_1") (pintype "passive"))
      (node (ref "R8") (pin "2") (pinfunction "2_2") (pintype "passive"))
    )
    (net (code "42") (name "Net-(R31-Pad1)") (class "Default")
      (node (ref "R31") (pin "1") (pinfunction "1_1") (pintype "passive"))
      (node (ref "U1") (pin "38") (pinfunction "RSVD_38") (pintype "passive"))
    )
    (net (code "43") (name "Net-(R32-Pad1)") (class "Default")
      (node (ref "R32") (pin "1") (pinfunction "1_1") (pintype "passive"))
      (node (ref "U1") (pin "39") (pinfunction "RSVD_39") (pintype "passive"))
    )
    (net (code "44") (name "Net-(R33-Pad1)") (class "Default")
      (node (ref "R33") (pin "1") (pinfunction "1_1") (pintype "passive"))
      (node (ref "U1") (pin "40") (pinfunction "RSVD_40") (pintype "passive"))
    )
    (net (code "45") (name "Net-(R34-Pad1)") (class "Default")
      (node (ref "R34") (pin "1") (pinfunction "1_1") (pintype "passive"))
      (node (ref "U1") (pin "41") (pinfunction "RSVD_41") (pintype "passive"))
    )
    (net (code "46") (name "Net-(R35-Pad1)") (class "Default")
      (node (ref "R35") (pin "1") (pinfunction "1_1") (pintype "passive"))
      (node (ref "U1") (pin "42") (pinfunction "RSVD_42") (pintype "passive"))
    )
    (net (code "47") (name "Net-(R40-Pad2)") (class "Default")
      (node (ref "R40") (pin "2") (pinfunction "2_2") (pintype "passive"))
      (node (ref "U1") (pin "23") (pinfunction "RSVD_23") (pintype "passive"))
    )
    (net (code "48") (name "Net-(U1-1V2O)") (class "Default")
      (node (ref "C18") (pin "2") (pinfunction "2_2") (pintype "passive"))
      (node (ref "U1") (pin "22") (pinfunction "1V2O_22") (pintype "passive"))
    )
    (net (code "49") (name "Net-(U1-EXRES1)") (class "Default")
      (node (ref "R39") (pin "1") (pinfunction "1_1") (pintype "passive"))
      (node (ref "U1") (pin "10") (pinfunction "EXRES1_10") (pintype "passive"))
    )
    (net (code "50") (name "Net-(U1-PMODE0)") (class "Default")
      (node (ref "R38") (pin "1") (pinfunction "1_1") (pintype "passive"))
      (node (ref "U1") (pin "45") (pinfunction "PMODE0_45") (pintype "passive"))
    )
    (net (code "51") (name "Net-(U1-PMODE1)") (class "Default")
      (node (ref "R37") (pin "1") (pinfunction "1_1") (pintype "passive"))
      (node (ref "U1") (pin "44") (pinfunction "PMODE1_44") (pintype "passive"))
    )
    (net (code "52") (name "Net-(U1-PMODE2)") (class "Default")
      (node (ref "R36") (pin "1") (pinfunction "1_1") (pintype "passive"))
      (node (ref "U1") (pin "43") (pinfunction "PMODE2_43") (pintype "passive"))
    )
    (net (code "53") (name "Net-(U1-TOCAP)") (class "Default")
      (node (ref "C19") (pin "2") (pinfunction "2_2") (pintype "passive"))
      (node (ref "U1") (pin "20") (pinfunction "TOCAP_20") (pintype "passive"))
    )
    (net (code "54") (name "Net-(X9-A-R)") (class "Default")
      (node (ref "R29") (pin "1") (pinfunction "1_1") (pintype "passive"))
      (node (ref "X9") (pin "9") (pinfunction "A-R_9") (pintype "passive"))
    )
    (net (code "55") (name "Net-(X9-AL)") (class "Default")
      (node (ref "R28") (pin "1") (pinfunction "1_1") (pintype "passive"))
      (node (ref "X9") (pin "12") (pinfunction "AL_12") (pintype "passive"))
    )
    (net (code "56") (name "Net-(X9-CR)") (class "Default")
      (node (ref "C22") (pin "1") (pinfunction "1_1") (pintype "passive"))
      (node (ref "R26") (pin "2") (pinfunction "2_2") (pintype "passive"))
      (node (ref "R27") (pin "2") (pinfunction "2_2") (pintype "passive"))
      (node (ref "X9") (pin "6") (pinfunction "CR_6") (pintype "input"))
    )
    (net (code "57") (name "Net-(X9-CT)") (class "Default")
      (node (ref "C10") (pin "1") (pinfunction "1_1") (pintype "passive"))
      (node (ref "R23") (pin "1") (pinfunction "1_1") (pintype "passive"))
      (node (ref "X9") (pin "3") (pinfunction "CT_3") (pintype "input"))
    )
    (net (code "58") (name "Net-(X9-RD+)") (class "Default")
      (node (ref "C15") (pin "2") (pinfunction "2_2") (pintype "passive"))
      (node (ref "X9") (pin "7") (pinfunction "RD+_7") (pintype "input"))
    )
    (net (code "59") (name "Net-(X9-RD-)") (class "Default")
      (node (ref "C21") (pin "2") (pinfunction "2_2") (pintype "passive"))
      (node (ref "X9") (pin "8") (pinfunction "RD-_8") (pintype "input"))
    )
    (net (code "60") (name "Net-(XB1-~{CTS}{slash}DIO7)") (class "Default")
      (node (ref "XB1") (pin "12") (pinfunction "~{CTS}/DIO7_12") (pintype "bidirectional"))
      (node (ref "XB1") (pin "16") (pinfunction "~{RTS}/AD6/DIO6_16") (pintype "bidirectional"))
    )
    (net (code "61") (name "RESET") (class "Default")
      (node (ref "IC4") (pin "30") (pinfunction "RUN_30") (pintype "bidirectional"))
      (node (ref "U$2") (pin "1") (pinfunction "~{RST}_1") (pintype "bidirectional"))
    )
    (net (code "62") (name "RG-11") (class "Default")
      (node (ref "IC4") (pin "17") (pinfunction "UART0_RX/I2C0_SCL_/SPI1_CSN/GP13_17") (pintype "bidirectional"))
      (node (ref "IC5") (pin "P$13") (pinfunction "B5_P$13") (pintype "bidirectional"))
    )
    (net (code "63") (name "RG-11-IN_5V") (class "Default")
      (node (ref "C1") (pin "1") (pinfunction "1_1") (pintype "passive"))
      (node (ref "IC5") (pin "P$7") (pinfunction "A5_P$7") (pintype "bidirectional"))
      (node (ref "R4") (pin "1") (pinfunction "1_1") (pintype "passive"))
      (node (ref "R5") (pin "1") (pinfunction "1_1") (pintype "passive"))
    )
    (net (code "64") (name "RG-11-IN_EXT") (class "Default")
      (node (ref "R5") (pin "2") (pinfunction "2_2") (pintype "passive"))
      (node (ref "X5") (pin "2") (pinfunction "KL_2") (pintype "passive"))
    )
    (net (code "65") (name "RX2") (class "Default")
      (node (ref "IC3") (pin "1") (pinfunction "TXD_1") (pintype "output"))
      (node (ref "IC4") (pin "12") (pinfunction "UART1_RX/I2C0_SCL_/SPI1_CSN/GP9_12") (pintype "bidirectional"))
    )
    (net (code "66") (name "RXN") (class "Default")
      (node (ref "C21") (pin "1") (pinfunction "1_1") (pintype "passive"))
      (node (ref "R26") (pin "1") (pinfunction "1_1") (pintype "passive"))
      (node (ref "U1") (pin "5") (pinfunction "RXN_5") (pintype "passive"))
    )
    (net (code "67") (name "RXP") (class "Default")
      (node (ref "C15") (pin "1") (pinfunction "1_1") (pintype "passive"))
      (node (ref "R27") (pin "1") (pinfunction "1_1") (pintype "passive"))
      (node (ref "U1") (pin "6") (pinfunction "RXP_6") (pintype "passive"))
    )
    (net (code "68") (name "SCL") (class "Default")
      (node (ref "IC2") (pin "6") (pinfunction "SCL_6") (pintype "bidirectional"))
      (node (ref "IC4") (pin "7") (pinfunction "UART1_RX/I2C0_SCL_/SPI0_CSN/GP5_7") (pintype "bidirectional"))
      (node (ref "R1") (pin "1") (pinfunction "1_1") (pintype "passive"))
    )
    (net (code "69") (name "SCLK") (class "Default")
      (node (ref "IC4") (pin "24") (pinfunction "I2C1_SDA/_SPI0_SCK/GP18_24") (pintype "bidirectional"))
      (node (ref "U1") (pin "33") (pinfunction "SCLK_33") (pintype "passive"))
    )
    (net (code "70") (name "SDA") (class "Default")
      (node (ref "IC2") (pin "5") (pinfunction "SDA_5") (pintype "bidirectional"))
      (node (ref "IC4") (pin "6") (pinfunction "UART1_TX/I2C0_SDA_/SPI0_RX/GP4_6") (pintype "bidirectional"))
      (node (ref "R3") (pin "1") (pinfunction "1_1") (pintype "passive"))
    )
    (net (code "71") (name "SDI") (class "Default")
      (node (ref "IC4") (pin "21") (pinfunction "UART0_TX/I2C0_SDA_/SPI0_RX_/GP16_21") (pintype "bidirectional"))
      (node (ref "U1") (pin "34") (pinfunction "MISO_34") (pintype "passive"))
    )
    (net (code "72") (name "SDO") (class "Default")
      (node (ref "IC4") (pin "25") (pinfunction "I2C1_SCL/_SPI0_TX/GP19_25") (pintype "bidirectional"))
      (node (ref "U1") (pin "35") (pinfunction "MOSI_35") (pintype "passive"))
    )
    (net (code "73") (name "SHUTTER_OPENED") (class "Default")
      (node (ref "IC4") (pin "19") (pinfunction "I2C1_SDA/SPI1_SCK/GP14_19") (pintype "bidirectional"))
      (node (ref "IC5") (pin "P$12") (pinfunction "B6_P$12") (pintype "bidirectional"))
    )
    (net (code "74") (name "SHUTTER_OPENED-IN_EXT") (class "Default")
      (node (ref "R48") (pin "2") (pinfunction "2_2") (pintype "passive"))
      (node (ref "X3") (pin "2") (pinfunction "KL_2") (pintype "passive"))
    )
    (net (code "75") (name "SHUTTER_OPENED_IN_5V") (class "Default")
      (node (ref "C44") (pin "1") (pinfunction "1_1") (pintype "passive"))
      (node (ref "IC5") (pin "P$8") (pinfunction "A6_P$8") (pintype "bidirectional"))
      (node (ref "R17") (pin "2") (pinfunction "2_2") (pintype "passive"))
      (node (ref "R48") (pin "1") (pinfunction "1_1") (pintype "passive"))
    )
    (net (code "76") (name "SPARE1") (class "Default")
      (node (ref "IC4") (pin "9") (pinfunction "I2C1_SDA_/SPI0_SCK/GP6_9") (pintype "bidirectional"))
      (node (ref "IC5") (pin "P$18") (pinfunction "B0_P$18") (pintype "bidirectional"))
    )
    (net (code "77") (name "SPARE1-IN_EXT") (class "Default")
      (node (ref "R45") (pin "2") (pinfunction "2_2") (pintype "passive"))
      (node (ref "X8") (pin "1") (pinfunction "KL_1") (pintype "passive"))
    )
    (net (code "78") (name "SPARE1_IN_5V") (class "Default")
      (node (ref "C41") (pin "1") (pinfunction "1_1") (pintype "passive"))
      (node (ref "IC5") (pin "P$2") (pinfunction "A0_P$2") (pintype "bidirectional"))
      (node (ref "R21") (pin "2") (pinfunction "2_2") (pintype "passive"))
      (node (ref "R45") (pin "1") (pinfunction "1_1") (pintype "passive"))
    )
    (net (code "79") (name "SPARE2") (class "Default")
      (node (ref "IC4") (pin "16") (pinfunction "UART0_TX/I2C0_SDA_/SPI1_RX_/GP12_16") (pintype "bidirectional"))
      (node (ref "IC5") (pin "P$14") (pinfunction "B4_P$14") (pintype "bidirectional"))
    )
    (net (code "80") (name "SPARE2-IN_EXT") (class "Default")
      (node (ref "R49") (pin "2") (pinfunction "2_2") (pintype "passive"))
      (node (ref "X8") (pin "2") (pinfunction "KL_2") (pintype "passive"))
    )
    (net (code "81") (name "SPARE2_IN_5V") (class "Default")
      (node (ref "C45") (pin "1") (pinfunction "1_1") (pintype "passive"))
      (node (ref "IC5") (pin "P$6") (pinfunction "A4_P$6") (pintype "bidirectional"))
      (node (ref "R49") (pin "1") (pinfunction "1_1") (pintype "passive"))
      (node (ref "R9") (pin "2") (pinfunction "2_2") (pintype "passive"))
    )
    (net (code "82") (name "TX2") (class "Default")
      (node (ref "IC3") (pin "5") (pinfunction "RXD_5") (pintype "input"))
      (node (ref "IC4") (pin "11") (pinfunction "UART1_TX/I2C0_SDA_/SPI1_RX/GP8_11") (pintype "bidirectional"))
    )
    (net (code "83") (name "TXN") (class "Default")
      (node (ref "R25") (pin "1") (pinfunction "1_1") (pintype "passive"))
      (node (ref "U1") (pin "1") (pinfunction "TXN_1") (pintype "passive"))
      (node (ref "X9") (pin "2") (pinfunction "TD-_2") (pintype "input"))
    )
    (net (code "84") (name "TXP") (class "Default")
      (node (ref "R24") (pin "1") (pinfunction "1_1") (pintype "passive"))
      (node (ref "U1") (pin "2") (pinfunction "TXP_2") (pintype "passive"))
      (node (ref "X9") (pin "1") (pinfunction "TD+_1") (pintype "input"))
    )
    (net (code "85") (name "USBD_N") (class "Default")
      (node (ref "IC3") (pin "16") (pinfunction "USBDM_16") (pintype "bidirectional"))
      (node (ref "X13") (pin "2") (pinfunction "2_2") (pintype "passive"))
    )
    (net (code "86") (name "USBD_P") (class "Default")
      (node (ref "IC3") (pin "15") (pinfunction "USBDP_15") (pintype "bidirectional"))
      (node (ref "X13") (pin "3") (pinfunction "3_3") (pintype "passive"))
    )
    (net (code "87") (name "USB_VCC") (class "Default")
      (node (ref "X13") (pin "1") (pinfunction "1_1") (pintype "passive"))
    )
    (net (code "88") (name "VCC") (class "Default")
      (node (ref "C23") (pin "1") (pinfunction "1_1") (pintype "passive"))
      (node (ref "C28") (pin "1") (pinfunction "1_1") (pintype "passive"))
      (node (ref "C6") (pin "1") (pinfunction "1_1") (pintype "passive"))
      (node (ref "C7") (pin "1") (pinfunction "1_1") (pintype "passive"))
      (node (ref "IC3") (pin "20") (pinfunction "VCC_20") (pintype "power_in"))
      (node (ref "IC4") (pin "39") (pinfunction "VSYS_39") (pintype "bidirectional"))
      (node (ref "IC6") (pin "P$1") (pinfunction "DIR_P$1") (pintype "input"))
      (node (ref "IC6") (pin "P$20") (pinfunction "VDD_P$20") (pintype "power_in"))
      (node (ref "IC8") (pin "3") (pinfunction "VIN_3") (pintype "input"))
      (node (ref "IC9") (pin "2") (pinfunction "VOUT_2") (pintype "output"))
      (node (ref "R13") (pin "2") (pinfunction "2_2") (pintype "passive"))
      (node (ref "R14") (pin "1") (pinfunction "1_1") (pintype "passive"))
      (node (ref "R15") (pin "1") (pinfunction "1_1") (pintype "passive"))
      (node (ref "R16") (pin "1") (pinfunction "1_1") (pintype "passive"))
      (node (ref "R17") (pin "1") (pinfunction "1_1") (pintype "passive"))
      (node (ref "R18") (pin "1") (pinfunction "1_1") (pintype "passive"))
      (node (ref "R19") (pin "1") (pinfunction "1_1") (pintype "passive"))
      (node (ref "R20") (pin "2") (pinfunction "2_2") (pintype "passive"))
      (node (ref "R21") (pin "1") (pinfunction "1_1") (pintype "passive"))
      (node (ref "R4") (pin "2") (pinfunction "2_2") (pintype "passive"))
      (node (ref "R9") (pin "1") (pinfunction "1_1") (pintype "passive"))
      (node (ref "X10") (pin "3") (pinfunction "KL_3") (pintype "passive"))
      (node (ref "X2") (pin "3") (pinfunction "KL_3") (pintype "passive"))
      (node (ref "X6") (pin "3") (pinfunction "KL_3") (pintype "passive"))
    )
    (net (code "89") (name "VPIN") (class "Default")
      (node (ref "IC4") (pin "31") (pinfunction "I2C1_SDA/ADC0/GP26_31") (pintype "bidirectional"))
      (node (ref "R2") (pin "1") (pinfunction "1_1") (pintype "passive"))
      (node (ref "R6") (pin "2") (pinfunction "2_2") (pintype "passive"))
    )
    (net (code "90") (name "XBEE_DIN") (class "Default")
      (node (ref "IC4") (pin "1") (pinfunction "UART0_TX/I2C0_SDA_/SPI0_RX/GP0_1") (pintype "bidirectional"))
      (node (ref "XB1") (pin "3") (pinfunction "DIN/~{CONFIG}_3") (pintype "input"))
    )
    (net (code "91") (name "XBEE_DOUT") (class "Default")
      (node (ref "IC4") (pin "2") (pinfunction "UART0_RX/I2C0_SCL_/SPI0_CSN/GP1_2") (pintype "bidirectional"))
      (node (ref "XB1") (pin "2") (pinfunction "DOUT_2") (pintype "output"))
    )
    (net (code "92") (name "XBEE_RESET") (class "Default")
      (node (ref "IC4") (pin "29") (pinfunction "GP22_29") (pintype "bidirectional"))
      (node (ref "XB1") (pin "5") (pinfunction "~{RESET}_5") (pintype "input"))
    )
    (net (code "93") (name "XI") (class "Default")
      (node (ref "25MHZ") (pin "3") (pinfunction "FO_3") (pintype "output"))
      (node (ref "U1") (pin "30") (pinfunction "XI/CLKIN_30") (pintype "passive"))
    )
    (net (code "94") (name "XO") (class "Default")
      (node (ref "U1") (pin "31") (pinfunction "XO_31") (pintype "passive"))
    )
    (net (code "95") (name "unconnected-(IC2-WP-Pad7)") (class "Default")
      (node (ref "IC2") (pin "7") (pinfunction "WP_7") (pintype "bidirectional"))
    )
    (net (code "96") (name "unconnected-(IC3-CBUS0-Pad23)") (class "Default")
      (node (ref "IC3") (pin "23") (pinfunction "CBUS0_23") (pintype "bidirectional"))
    )
    (net (code "97") (name "unconnected-(IC3-CBUS1-Pad22)") (class "Default")
      (node (ref "IC3") (pin "22") (pinfunction "CBUS1_22") (pintype "bidirectional"))
    )
    (net (code "98") (name "unconnected-(IC3-CBUS2-Pad13)") (class "Default")
      (node (ref "IC3") (pin "13") (pinfunction "CBUS2_13") (pintype "bidirectional"))
    )
    (net (code "99") (name "unconnected-(IC3-CBUS3-Pad14)") (class "Default")
      (node (ref "IC3") (pin "14") (pinfunction "CBUS3_14") (pintype "bidirectional"))
    )
    (net (code "100") (name "unconnected-(IC3-CBUS4-Pad12)") (class "Default")
      (node (ref "IC3") (pin "12") (pinfunction "CBUS4_12") (pintype "bidirectional"))
    )
    (net (code "101") (name "unconnected-(IC3-OSCI-Pad27)") (class "Default")
      (node (ref "IC3") (pin "27") (pinfunction "OSCI_27") (pintype "input"))
    )
    (net (code "102") (name "unconnected-(IC3-OSCO-Pad28)") (class "Default")
      (node (ref "IC3") (pin "28") (pinfunction "OSCO_28") (pintype "output"))
    )
    (net (code "103") (name "unconnected-(IC3-TEST-Pad26)") (class "Default")
      (node (ref "IC3") (pin "26") (pinfunction "TEST_26") (pintype "input"))
    )
    (net (code "104") (name "unconnected-(IC3-~{RI}-Pad6)") (class "Default")
      (node (ref "IC3") (pin "6") (pinfunction "~{RI}_6") (pintype "input"))
    )
    (net (code "105") (name "unconnected-(IC6A-B4-PadP$14)") (class "Default")
      (node (ref "IC6") (pin "P$14") (pinfunction "B4_P$14") (pintype "bidirectional"))
    )
    (net (code "106") (name "unconnected-(IC6A-B5-PadP$13)") (class "Default")
      (node (ref "IC6") (pin "P$13") (pinfunction "B5_P$13") (pintype "bidirectional"))
    )
    (net (code "107") (name "unconnected-(IC6A-B6-PadP$12)") (class "Default")
      (node (ref "IC6") (pin "P$12") (pinfunction "B6_P$12") (pintype "bidirectional"))
    )
    (net (code "108") (name "unconnected-(IC6A-B7-PadP$11)") (class "Default")
      (node (ref "IC6") (pin "P$11") (pinfunction "B7_P$11") (pintype "bidirectional"))
    )
    (net (code "109") (name "unconnected-(J2-Pad3)") (class "Default")
      (node (ref "J2") (pin "3") (pinfunction "3_3") (pintype "bidirectional"))
    )
    (net (code "110") (name "unconnected-(J2-Pad4)") (class "Default")
      (node (ref "J2") (pin "4") (pinfunction "4_4") (pintype "bidirectional"))
    )
    (net (code "111") (name "unconnected-(U1-DNC-Pad7)") (class "Default")
      (node (ref "U1") (pin "7") (pinfunction "DNC_7") (pintype "passive"))
    )
    (net (code "112") (name "unconnected-(U1-DUPLED-Pad26)") (class "Default")
      (node (ref "U1") (pin "26") (pinfunction "DUPLED_26") (pintype "passive"))
    )
    (net (code "113") (name "unconnected-(U1-NC-Pad12)") (class "Default")
      (node (ref "U1") (pin "12") (pinfunction "NC_12") (pintype "passive"))
    )
    (net (code "114") (name "unconnected-(U1-NC-Pad13)") (class "Default")
      (node (ref "U1") (pin "13") (pinfunction "NC_13") (pintype "passive"))
    )
    (net (code "115") (name "unconnected-(U1-NC-Pad46)") (class "Default")
      (node (ref "U1") (pin "46") (pinfunction "NC_46") (pintype "passive"))
    )
    (net (code "116") (name "unconnected-(U1-NC-Pad47)") (class "Default")
      (node (ref "U1") (pin "47") (pinfunction "NC_47") (pintype "passive"))
    )
    (net (code "117") (name "unconnected-(U1-SPDLED-Pad24)") (class "Default")
      (node (ref "U1") (pin "24") (pinfunction "SPDLED_24") (pintype "passive"))
    )
    (net (code "118") (name "unconnected-(U1-VBG-Pad18)") (class "Default")
      (node (ref "U1") (pin "18") (pinfunction "VBG_18") (pintype "passive"))
    )
    (net (code "119") (name "unconnected-(XB1-AD0{slash}DIO0-Pad20)") (class "Default")
      (node (ref "XB1") (pin "20") (pinfunction "AD0/DIO0_20") (pintype "bidirectional"))
    )
    (net (code "120") (name "unconnected-(XB1-AD1{slash}DIO1-Pad19)") (class "Default")
      (node (ref "XB1") (pin "19") (pinfunction "AD1/DIO1_19") (pintype "bidirectional"))
    )
    (net (code "121") (name "unconnected-(XB1-AD2{slash}DIO2-Pad18)") (class "Default")
      (node (ref "XB1") (pin "18") (pinfunction "AD2/DIO2_18") (pintype "bidirectional"))
    )
    (net (code "122") (name "unconnected-(XB1-ASSOC{slash}AD5{slash}DIO5-Pad15)") (class "Default")
      (node (ref "XB1") (pin "15") (pinfunction "ASSOC/AD5/DIO5_15") (pintype "bidirectional"))
    )
    (net (code "123") (name "unconnected-(XB1-CD{slash}DOUT_EN{slash}DO8-Pad4)") (class "Default")
      (node (ref "XB1") (pin "4") (pinfunction "CD/DOUT_EN/DO8_4") (pintype "output"))
    )
    (net (code "124") (name "unconnected-(XB1-COORD_SEL{slash}AD3{slash}DIO3-Pad17)") (class "Default")
      (node (ref "XB1") (pin "17") (pinfunction "COORD_SEL/AD3/DIO3_17") (pintype "bidirectional"))
    )
    (net (code "125") (name "unconnected-(XB1-ON{slash}~{SLEEP}-Pad13)") (class "Default")
      (node (ref "XB1") (pin "13") (pinfunction "ON/~{SLEEP}_13") (pintype "output"))
    )
    (net (code "126") (name "unconnected-(XB1-PWM0{slash}RSSI-Pad6)") (class "Default")
      (node (ref "XB1") (pin "6") (pinfunction "PWM0/RSSI_6") (pintype "output"))
    )
    (net (code "127") (name "unconnected-(XB1-RF_TX{slash}AD4{slash}DIO4-Pad11)") (class "Default")
      (node (ref "XB1") (pin "11") (pinfunction "RF_TX/AD4/DIO4_11") (pintype "bidirectional"))
    )
    (net (code "128") (name "unconnected-(XB1-VREF-Pad14)") (class "Default")
      (node (ref "XB1") (pin "14") (pinfunction "VREF_14") (pintype "input"))
    )
  )
)
